# Switch.net
KiCad netlist of a schematic drawn in Altium Designer
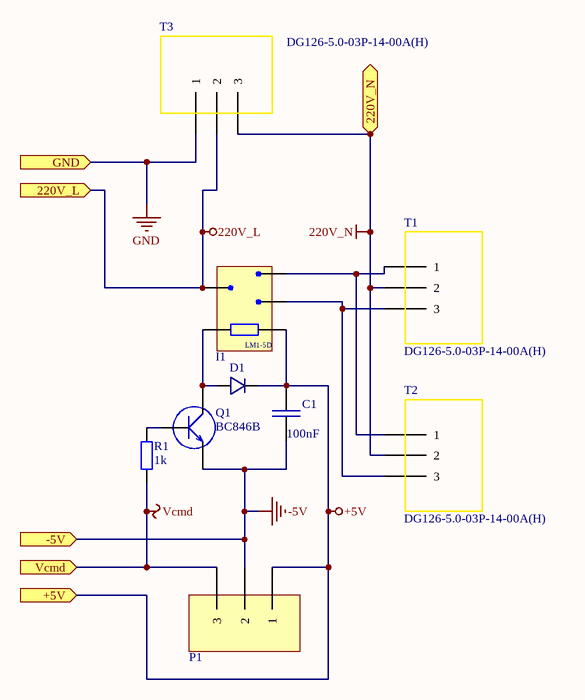
[diagram p0: Switch.SchDoc]

(export (version "E")
  (design (tool "Eeschema 10.0.6"))
  (components
    (comp (ref "C1")
      (value "100nF")
      (footprint "SMD-0805")
      (description "Condensator: ceramic; 100nF; 50V; X7R; ±10%; SMD; 0805; -55÷125°C")
      (libsource (lib "GenericComponents") (part "C-100nF-0805"))
    )
    (comp (ref "D1")
      (value "BAS16")
      (footprint "SOT-23")
      (description "Dioda: comutatie; 75V; 50mA; 100mA; SOT23; 6ns")
      (libsource (lib "GenericComponents") (part "BAS16"))
    )
    (comp (ref "I1")
      (value "I-LM1-5D")
      (footprint "LM1-5D")
      (description "Releu: electromagnetic; SPDT; Ubobina:5VDC; 12A/250VAC; 12A/30VDC")
      (libsource (lib "GenericComponents") (part "I-LM1-5D"))
    )
    (comp (ref "P1")
      (value "Pins 3")
      (footprint "THT3-254")
      (libsource (lib "GenericComponents") (part "Pins 3"))
    )
    (comp (ref "Q1")
      (value "BC846B")
      (footprint "SOT-23")
      (description "Tranzistor: bipolar, NPN; 65V; 100mA; SOT23")
      (libsource (lib "GenericComponents") (part "BC846B"))
    )
    (comp (ref "R1")
      (value "1k")
      (footprint "SMD-0805")
      (description "Rezistor: thick film; SMD; 0805; 1kO; 0,125W; ±5%; -55÷155°C")
      (fields (field (name "Comment") "1K"))
      (libsource (lib "GenericComponents") (part "R-1K-0805"))
    )
    (comp (ref "T1")
      (value "DG126-5.0-03P-14-00A(H)")
      (footprint "DG126-5.0-03P-14-00A(H)")
      (description "Connector")
      (libsource (lib "GenericComponents") (part "DG126-5.0-03P-14-00A(H)"))
    )
    (comp (ref "T2")
      (value "DG126-5.0-03P-14-00A(H)")
      (footprint "DG126-5.0-03P-14-00A(H)")
      (description "Connector")
      (libsource (lib "GenericComponents") (part "DG126-5.0-03P-14-00A(H)"))
    )
    (comp (ref "T3")
      (value "DG126-5.0-03P-14-00A(H)")
      (footprint "DG126-5.0-03P-14-00A(H)")
      (description "Connector")
      (libsource (lib "GenericComponents") (part "DG126-5.0-03P-14-00A(H)"))
    )
  )
  (nets
    (net (code "1") (name "+5V") (class "Default")
      (node (ref "C1") (pin "1") (pinfunction "1_1") (pintype "passive"))
      (node (ref "D1") (pin "1") (pinfunction "C_1") (pintype "passive"))
      (node (ref "I1") (pin "1") (pinfunction "1_1") (pintype "passive"))
      (node (ref "P1") (pin "1") (pinfunction "1_1") (pintype "passive"))
    )
    (net (code "2") (name "-5V") (class "Default")
      (node (ref "C1") (pin "2") (pinfunction "2_2") (pintype "passive"))
      (node (ref "P1") (pin "2") (pinfunction "2_2") (pintype "passive"))
      (node (ref "Q1") (pin "2") (pinfunction "E_2") (pintype "passive"))
    )
    (net (code "3") (name "220V_L") (class "Default")
      (node (ref "I1") (pin "3") (pinfunction "3_3") (pintype "passive"))
      (node (ref "T3") (pin "2") (pinfunction "2_2") (pintype "passive"))
    )
    (net (code "4") (name "220V_N") (class "Default")
      (node (ref "T1") (pin "2") (pinfunction "2_2") (pintype "passive"))
      (node (ref "T2") (pin "2") (pinfunction "2_2") (pintype "passive"))
      (node (ref "T3") (pin "3") (pinfunction "3_3") (pintype "passive"))
    )
    (net (code "5") (name "GND") (class "Default")
      (node (ref "T3") (pin "1") (pinfunction "1_1") (pintype "passive"))
    )
    (net (code "6") (name "Net-(D1-A)") (class "Default")
      (node (ref "D1") (pin "3") (pinfunction "A_3") (pintype "passive"))
      (node (ref "I1") (pin "2") (pinfunction "2_2") (pintype "passive"))
      (node (ref "Q1") (pin "3") (pinfunction "C_3") (pintype "passive"))
    )
    (net (code "7") (name "Net-(I1-Pad4)") (class "Default")
      (node (ref "I1") (pin "4") (pinfunction "4_4") (pintype "passive"))
      (node (ref "T1") (pin "1") (pinfunction "1_1") (pintype "passive"))
      (node (ref "T2") (pin "1") (pinfunction "1_1") (pintype "passive"))
    )
    (net (code "8") (name "Net-(I1-Pad5)") (class "Default")
      (node (ref "I1") (pin "5") (pinfunction "5_5") (pintype "passive"))
      (node (ref "T1") (pin "3") (pinfunction "3_3") (pintype "passive"))
      (node (ref "T2") (pin "3") (pinfunction "3_3") (pintype "passive"))
    )
    (net (code "9") (name "Net-(Q1-B)") (class "Default")
      (node (ref "Q1") (pin "1") (pinfunction "B_1") (pintype "passive"))
      (node (ref "R1") (pin "1") (pinfunction "1_1") (pintype "passive"))
    )
    (net (code "10") (name "Vcmd") (class "Default")
      (node (ref "P1") (pin "3") (pinfunction "3_3") (pintype "passive"))
      (node (ref "R1") (pin "2") (pinfunction "2_2") (pintype "passive"))
    )
  )
)
